# direct-drive-sampler.net
KiCad netlist of a schematic drawn in EAGLE
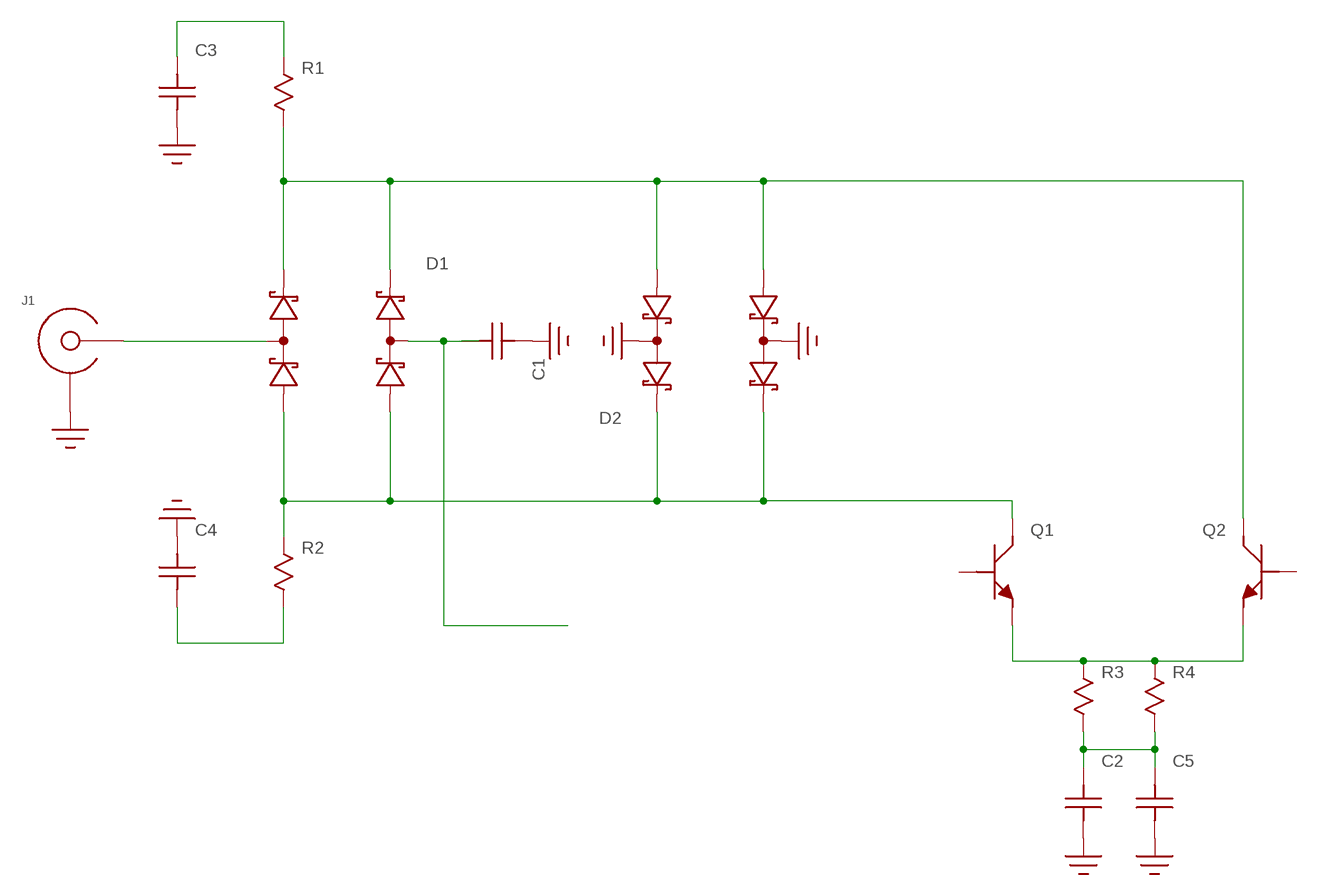
[diagram p0: schematic, sheet 1]

(export (version "E")
  (design (tool "Eeschema 10.0.6"))
  (components
    (comp (ref "C1") (value "C") (footprint "eagle-import:C0402") (libsource (lib "eagle-import") (part "C")))
    (comp (ref "C2") (value "C") (footprint "eagle-import:C0402") (libsource (lib "eagle-import") (part "C")))
    (comp (ref "C3") (value "C") (footprint "eagle-import:C0402") (libsource (lib "eagle-import") (part "C")))
    (comp (ref "C4") (value "C") (footprint "eagle-import:C0402") (libsource (lib "eagle-import") (part "C")))
    (comp (ref "C5") (value "C") (footprint "eagle-import:C0402") (libsource (lib "eagle-import") (part "C")))
    (comp (ref "D1")
      (value "SMS3923-081")
      (footprint "eagle-import:SC-88")
      (libsource (lib "eagle-import") (part "SMS3923-081"))
    )
    (comp (ref "D2")
      (value "SMS3923-081")
      (footprint "eagle-import:SC-88")
      (libsource (lib "eagle-import") (part "SMS3923-081"))
    )
    (comp (ref "J1")
      (value "SMA-EDGE-LAUNCH")
      (footprint "eagle-import:SMA_EDGE_LAUNCH_2L_4020_TAPER_FIXED")
      (libsource (lib "eagle-import") (part "SMA-EDGE-LAUNCH"))
    )
    (comp (ref "Q1")
      (value "NPN-BFP740")
      (footprint "eagle-import:SOT343")
      (libsource (lib "eagle-import") (part "NPN-BFP740"))
    )
    (comp (ref "Q2")
      (value "NPN-BFP740")
      (footprint "eagle-import:SOT343")
      (libsource (lib "eagle-import") (part "NPN-BFP740"))
    )
    (comp (ref "R1")
      (value "R0402")
      (footprint "eagle-import:0402")
      (libsource (lib "eagle-import") (part "R0402"))
    )
    (comp (ref "R2")
      (value "R0402")
      (footprint "eagle-import:0402")
      (libsource (lib "eagle-import") (part "R0402"))
    )
    (comp (ref "R3")
      (value "R0402")
      (footprint "eagle-import:0402")
      (libsource (lib "eagle-import") (part "R0402"))
    )
    (comp (ref "R4")
      (value "R0402")
      (footprint "eagle-import:0402")
      (libsource (lib "eagle-import") (part "R0402"))
    )
  )
  (nets
    (net (code "1") (name "GND") (class "Default")
      (node (ref "C1") (pin "2") (pinfunction "P$2_2") (pintype "bidirectional"))
      (node (ref "C2") (pin "1") (pinfunction "P$1_1") (pintype "bidirectional"))
      (node (ref "C3") (pin "1") (pinfunction "P$1_1") (pintype "bidirectional"))
      (node (ref "C4") (pin "2") (pinfunction "P$2_2") (pintype "bidirectional"))
      (node (ref "C5") (pin "1") (pinfunction "P$1_1") (pintype "bidirectional"))
      (node (ref "D2") (pin "2") (pinfunction "COMMON0_2") (pintype "bidirectional"))
      (node (ref "D2") (pin "5") (pinfunction "COMMON1_5") (pintype "bidirectional"))
      (node (ref "J1") (pin "BOTTOM_GND") (pinfunction "SHIELD_BOTTOM_GND") (pintype "bidirectional"))
      (node (ref "J1") (pin "GND@1") (pinfunction "SHIELD_GND@1") (pintype "bidirectional"))
      (node (ref "J1") (pin "GND@14") (pinfunction "SHIELD_GND@14") (pintype "bidirectional"))
      (node (ref "J1") (pin "GND@15") (pinfunction "SHIELD_GND@15") (pintype "bidirectional"))
      (node (ref "J1") (pin "GND@16") (pinfunction "SHIELD_GND@16") (pintype "bidirectional"))
      (node (ref "J1") (pin "GND@17") (pinfunction "SHIELD_GND@17") (pintype "bidirectional"))
      (node (ref "J1") (pin "GND@2") (pinfunction "SHIELD_GND@2") (pintype "bidirectional"))
      (node (ref "J1") (pin "GND@3") (pinfunction "SHIELD_GND@3") (pintype "bidirectional"))
      (node (ref "J1") (pin "GND@4") (pinfunction "SHIELD_GND@4") (pintype "bidirectional"))
      (node (ref "J1") (pin "GND@5") (pinfunction "SHIELD_GND@5") (pintype "bidirectional"))
      (node (ref "J1") (pin "GND@6") (pinfunction "SHIELD_GND@6") (pintype "bidirectional"))
      (node (ref "J1") (pin "GND@7") (pinfunction "SHIELD_GND@7") (pintype "bidirectional"))
      (node (ref "J1") (pin "GND@8") (pinfunction "SHIELD_GND@8") (pintype "bidirectional"))
      (node (ref "J1") (pin "GND_PAD1") (pinfunction "SHIELD_GND_PAD1") (pintype "bidirectional"))
      (node (ref "J1") (pin "GND_PAD2") (pinfunction "SHIELD_GND_PAD2") (pintype "bidirectional"))
      (node (ref "J1") (pin "P$1") (pinfunction "SHIELD_P$1") (pintype "bidirectional"))
      (node (ref "J1") (pin "P$2") (pinfunction "SHIELD_P$2") (pintype "bidirectional"))
    )
    (net (code "2") (name "Net-(C1-P$1)") (class "Default")
      (node (ref "C1") (pin "1") (pinfunction "P$1_1") (pintype "bidirectional"))
      (node (ref "D1") (pin "2") (pinfunction "COMMON0_2") (pintype "bidirectional"))
    )
    (net (code "3") (name "Net-(C2-P$2)") (class "Default")
      (node (ref "C2") (pin "2") (pinfunction "P$2_2") (pintype "bidirectional"))
      (node (ref "C5") (pin "2") (pinfunction "P$2_2") (pintype "bidirectional"))
      (node (ref "R3") (pin "2") (pinfunction "P$4_2") (pintype "bidirectional"))
      (node (ref "R4") (pin "2") (pinfunction "P$4_2") (pintype "bidirectional"))
    )
    (net (code "4") (name "Net-(C3-P$2)") (class "Default")
      (node (ref "C3") (pin "2") (pinfunction "P$2_2") (pintype "bidirectional"))
      (node (ref "R1") (pin "1") (pinfunction "P$3_1") (pintype "bidirectional"))
    )
    (net (code "5") (name "Net-(C4-P$1)") (class "Default")
      (node (ref "C4") (pin "1") (pinfunction "P$1_1") (pintype "bidirectional"))
      (node (ref "R2") (pin "2") (pinfunction "P$4_2") (pintype "bidirectional"))
    )
    (net (code "6") (name "Net-(D1-ANODE0)") (class "Default")
      (node (ref "D1") (pin "1") (pinfunction "ANODE0_1") (pintype "bidirectional"))
      (node (ref "D1") (pin "6") (pinfunction "ANODE1_6") (pintype "bidirectional"))
      (node (ref "D2") (pin "3") (pinfunction "CATHODE0_3") (pintype "bidirectional"))
      (node (ref "D2") (pin "4") (pinfunction "CATHODE1_4") (pintype "bidirectional"))
      (node (ref "Q1") (pin "3") (pinfunction "C_3") (pintype "bidirectional"))
      (node (ref "R2") (pin "1") (pinfunction "P$3_1") (pintype "bidirectional"))
    )
    (net (code "7") (name "Net-(D1-CATHODE0)") (class "Default")
      (node (ref "D1") (pin "3") (pinfunction "CATHODE0_3") (pintype "bidirectional"))
      (node (ref "D1") (pin "4") (pinfunction "CATHODE1_4") (pintype "bidirectional"))
      (node (ref "D2") (pin "1") (pinfunction "ANODE0_1") (pintype "bidirectional"))
      (node (ref "D2") (pin "6") (pinfunction "ANODE1_6") (pintype "bidirectional"))
      (node (ref "Q2") (pin "3") (pinfunction "C_3") (pintype "bidirectional"))
      (node (ref "R1") (pin "2") (pinfunction "P$4_2") (pintype "bidirectional"))
    )
    (net (code "8") (name "Net-(D1-COMMON1)") (class "Default")
      (node (ref "D1") (pin "5") (pinfunction "COMMON1_5") (pintype "bidirectional"))
      (node (ref "J1") (pin "CENTER@1") (pinfunction "CENTER_CENTER@1") (pintype "bidirectional"))
      (node (ref "J1") (pin "P$3") (pinfunction "CENTER_P$3") (pintype "bidirectional"))
    )
    (net (code "9") (name "Net-(R3-P$3)") (class "Default")
      (node (ref "Q1") (pin "2") (pinfunction "E_2") (pintype "bidirectional"))
      (node (ref "Q1") (pin "4") (pinfunction "E_4") (pintype "bidirectional"))
      (node (ref "Q2") (pin "2") (pinfunction "E_2") (pintype "bidirectional"))
      (node (ref "Q2") (pin "4") (pinfunction "E_4") (pintype "bidirectional"))
      (node (ref "R3") (pin "1") (pinfunction "P$3_1") (pintype "bidirectional"))
      (node (ref "R4") (pin "1") (pinfunction "P$3_1") (pintype "bidirectional"))
    )
    (net (code "10") (name "unconnected-(Q1-B-Pad1)") (class "Default")
      (node (ref "Q1") (pin "1") (pinfunction "B_1") (pintype "bidirectional"))
    )
    (net (code "11") (name "unconnected-(Q2-B-Pad1)") (class "Default")
      (node (ref "Q2") (pin "1") (pinfunction "B_1") (pintype "bidirectional"))
    )
  )
)
